# LED0805-4_Sch.net
KiCad netlist of a schematic drawn in Altium Designer
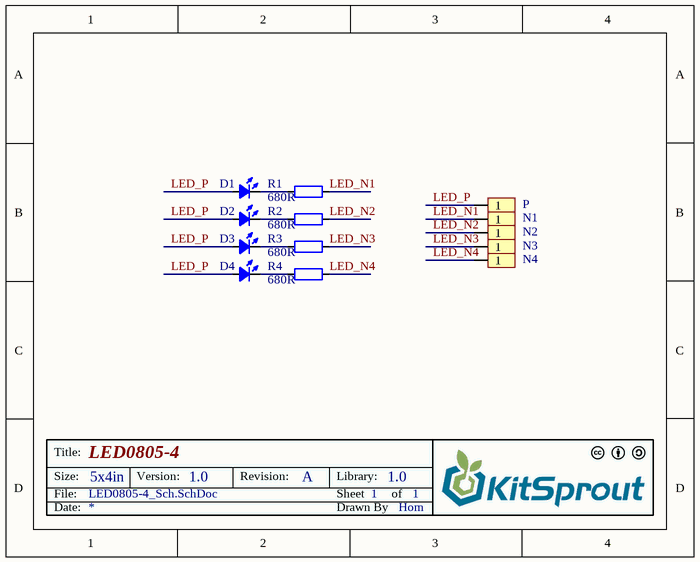
[diagram p0: LED0805-4_Sch.SchDoc]

(export (version "E")
  (design (tool "Eeschema 10.0.6"))
  (components
    (comp (ref "D1")
      (value "LED_0805")
      (footprint "PCB_ActiveLED:LED_0805_BLUE")
      (description "LED")
      (libsource (lib "SCH_Active") (part "LED_0805"))
    )
    (comp (ref "D2")
      (value "LED_0805")
      (footprint "PCB_ActiveLED:LED_0805_BLUE")
      (description "LED")
      (libsource (lib "SCH_Active") (part "LED_0805"))
    )
    (comp (ref "D3")
      (value "LED_0805")
      (footprint "PCB_ActiveLED:LED_0805_BLUE")
      (description "LED")
      (libsource (lib "SCH_Active") (part "LED_0805"))
    )
    (comp (ref "D4")
      (value "LED_0805")
      (footprint "PCB_ActiveLED:LED_0805_BLUE")
      (description "LED")
      (libsource (lib "SCH_Active") (part "LED_0805"))
    )
    (comp (ref "N1")
      (value "HDR-PAD_2.54")
      (footprint "PCB_ConnectorHDR:HDR-PAD_2.54")
      (description "Header")
      (libsource (lib "SCH_ConnectorHDR") (part "HDR-PAD_2.54"))
    )
    (comp (ref "N2")
      (value "HDR-PAD_2.54")
      (footprint "PCB_ConnectorHDR:HDR-PAD_2.54")
      (description "Header")
      (libsource (lib "SCH_ConnectorHDR") (part "HDR-PAD_2.54"))
    )
    (comp (ref "N3")
      (value "HDR-PAD_2.54")
      (footprint "PCB_ConnectorHDR:HDR-PAD_2.54")
      (description "Header")
      (libsource (lib "SCH_ConnectorHDR") (part "HDR-PAD_2.54"))
    )
    (comp (ref "N4")
      (value "HDR-PAD_2.54")
      (footprint "PCB_ConnectorHDR:HDR-PAD_2.54")
      (description "Header")
      (libsource (lib "SCH_ConnectorHDR") (part "HDR-PAD_2.54"))
    )
    (comp (ref "P")
      (value "HDR-PAD_2.54")
      (footprint "PCB_ConnectorHDR:HDR-PAD_2.54")
      (description "Header")
      (libsource (lib "SCH_ConnectorHDR") (part "HDR-PAD_2.54"))
    )
    (comp (ref "R1")
      (value "680R")
      (footprint "PCB_PassiveRes:RES_0805")
      (description "Resistor")
      (fields (field (name "Comment") "Res_0805"))
      (libsource (lib "SCH_Passive") (part "Res_0805"))
    )
    (comp (ref "R2")
      (value "680R")
      (footprint "PCB_PassiveRes:RES_0805")
      (description "Resistor")
      (fields (field (name "Comment") "Res_0805"))
      (libsource (lib "SCH_Passive") (part "Res_0805"))
    )
    (comp (ref "R3")
      (value "680R")
      (footprint "PCB_PassiveRes:RES_0805")
      (description "Resistor")
      (fields (field (name "Comment") "Res_0805"))
      (libsource (lib "SCH_Passive") (part "Res_0805"))
    )
    (comp (ref "R4")
      (value "680R")
      (footprint "PCB_PassiveRes:RES_0805")
      (description "Resistor")
      (fields (field (name "Comment") "Res_0805"))
      (libsource (lib "SCH_Passive") (part "Res_0805"))
    )
  )
  (nets
    (net (code "1") (name "/LED_N1") (class "Default")
      (node (ref "N1") (pin "1") (pinfunction "1_1") (pintype "passive"))
      (node (ref "R1") (pin "2") (pinfunction "2_2") (pintype "passive"))
    )
    (net (code "2") (name "/LED_N2") (class "Default")
      (node (ref "N2") (pin "1") (pinfunction "1_1") (pintype "passive"))
      (node (ref "R2") (pin "2") (pinfunction "2_2") (pintype "passive"))
    )
    (net (code "3") (name "/LED_N3") (class "Default")
      (node (ref "N3") (pin "1") (pinfunction "1_1") (pintype "passive"))
      (node (ref "R3") (pin "2") (pinfunction "2_2") (pintype "passive"))
    )
    (net (code "4") (name "/LED_N4") (class "Default")
      (node (ref "N4") (pin "1") (pinfunction "1_1") (pintype "passive"))
      (node (ref "R4") (pin "2") (pinfunction "2_2") (pintype "passive"))
    )
    (net (code "5") (name "/LED_P") (class "Default")
      (node (ref "D1") (pin "1") (pinfunction "A_1") (pintype "passive"))
      (node (ref "D2") (pin "1") (pinfunction "A_1") (pintype "passive"))
      (node (ref "D3") (pin "1") (pinfunction "A_1") (pintype "passive"))
      (node (ref "D4") (pin "1") (pinfunction "A_1") (pintype "passive"))
      (node (ref "P") (pin "1") (pinfunction "1_1") (pintype "passive"))
    )
    (net (code "6") (name "Net-(D1-K)") (class "Default")
      (node (ref "D1") (pin "2") (pinfunction "K_2") (pintype "passive"))
      (node (ref "R1") (pin "1") (pinfunction "1_1") (pintype "passive"))
    )
    (net (code "7") (name "Net-(D2-K)") (class "Default")
      (node (ref "D2") (pin "2") (pinfunction "K_2") (pintype "passive"))
      (node (ref "R2") (pin "1") (pinfunction "1_1") (pintype "passive"))
    )
    (net (code "8") (name "Net-(D3-K)") (class "Default")
      (node (ref "D3") (pin "2") (pinfunction "K_2") (pintype "passive"))
      (node (ref "R3") (pin "1") (pinfunction "1_1") (pintype "passive"))
    )
    (net (code "9") (name "Net-(D4-K)") (class "Default")
      (node (ref "D4") (pin "2") (pinfunction "K_2") (pintype "passive"))
      (node (ref "R4") (pin "1") (pinfunction "1_1") (pintype "passive"))
    )
  )
)
